# programmer.net
KiCad netlist of a schematic drawn in Altium Designer
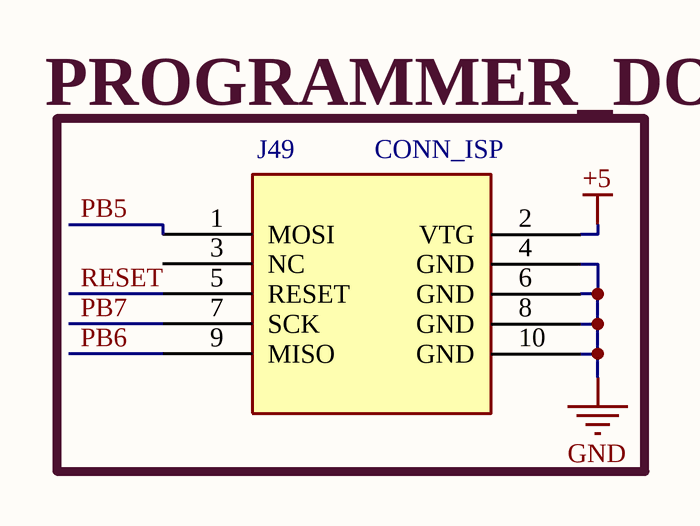
[diagram p0: programmer.SchDoc]

(export (version "E")
  (design (tool "Eeschema 10.0.6"))
  (components
    (comp (ref "J49")
      (value "CONN_ISP")
      (footprint "IDC_2X5")
      (description "CONN, ISP, AVR")
      (libsource (lib "conn_program") (part "CONN_AVR_ISP_IDC10"))
    )
  )
  (nets
    (net (code "1") (name "+5") (class "Default")
      (node (ref "J49") (pin "2") (pinfunction "VTG_2") (pintype "passive"))
    )
    (net (code "2") (name "/PB5") (class "Default")
      (node (ref "J49") (pin "1") (pinfunction "MOSI_1") (pintype "passive"))
    )
    (net (code "3") (name "/PB6") (class "Default")
      (node (ref "J49") (pin "9") (pinfunction "MISO_9") (pintype "passive"))
    )
    (net (code "4") (name "/PB7") (class "Default")
      (node (ref "J49") (pin "7") (pinfunction "SCK_7") (pintype "passive"))
    )
    (net (code "5") (name "/RESET") (class "Default")
      (node (ref "J49") (pin "5") (pinfunction "RESET_5") (pintype "passive"))
    )
    (net (code "6") (name "GND") (class "Default")
      (node (ref "J49") (pin "10") (pinfunction "GND_10") (pintype "passive"))
      (node (ref "J49") (pin "4") (pinfunction "GND_4") (pintype "passive"))
      (node (ref "J49") (pin "6") (pinfunction "GND_6") (pintype "passive"))
      (node (ref "J49") (pin "8") (pinfunction "GND_8") (pintype "passive"))
    )
    (net (code "7") (name "unconnected-(J49-NC-Pad3)") (class "Default")
      (node (ref "J49") (pin "3") (pinfunction "NC_3") (pintype "passive"))
    )
  )
)
